# Sheet3.net
KiCad netlist of a schematic drawn in Altium Designer
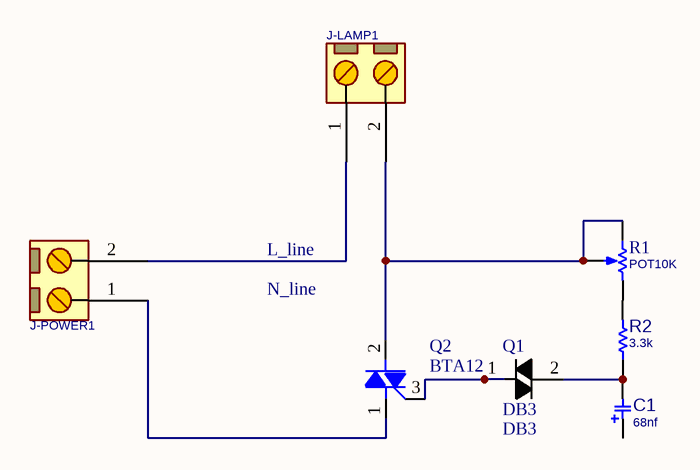
[diagram p0: Sheet3.SchDoc]

(export (version "E")
  (design (tool "Eeschema 10.0.6"))
  (components
    (comp (ref "C1")
      (value "68nf")
      (footprint "C_FLM_7X5H11")
      (description "CAP, THD, FILM,")
      (fields (field (name "MANF_P#") "MANF_PART#") (field (name "MANF") "MANF"))
      (libsource (lib "passive_thd") (part "CAP_THD_FLM"))
    )
    (comp (ref "J-LAMP1")
      (value "CONN_TB2")
      (footprint "MSTB_2")
      (description "CONN, PHOENIX MSTB, 5-G, 5.08mm pitch")
      (libsource (lib "conn_terminalB") (part "CONN_MSTB_2"))
    )
    (comp (ref "J-POWER1")
      (value "CONN_TB2")
      (footprint "MSTB_2")
      (description "CONN, PHOENIX MSTB, 5-G, 5.08mm pitch")
      (libsource (lib "") (part "CONN_MSTB_2_1"))
    )
    (comp (ref "Q1")
      (value "DB3")
      (footprint "D_AX03_DO35")
      (description "Diac, 32VBO, DO-35")
      (fields (field (name "MANF") "ST") (field (name "ALTIUM_VALUE") "DB3"))
      (libsource (lib "triac_diac") (part "DIAC_DB3_DO35"))
    )
    (comp (ref "Q2")
      (value "BTA12")
      (footprint "TO220_3")
      (description "Triac, 600V, 12A, TO-220")
      (fields (field (name "MANF_P#") "BTA12-600BW, BTA12-600CW, BTA12-600TW") (field (name "MANF") "ST"))
      (libsource (lib "triac_diac") (part "TRIAC_BTA12-600_TO220"))
    )
    (comp (ref "R1")
      (value "POT10K")
      (footprint "VOL_R")
      (description "RESISTOR, THD, Potentiometer Volume")
      (libsource (lib "resistor_pot_trimmer") (part "RES_THD_POT_VOL"))
    )
    (comp (ref "R2")
      (value "3.3k")
      (footprint "R025W_AX04")
      (description "RESISTOR, THD")
      (fields (field (name "MANF_P#") "RK73H1ETTP4701F") (field (name "MANF") "KOA SPEER"))
      (libsource (lib "passive_thd") (part "RES_THD"))
    )
  )
  (nets
    (net (code "1") (name "Net-(J-LAMP1-Pad1)") (class "Default")
      (node (ref "J-LAMP1") (pin "1") (pinfunction "1_1") (pintype "passive"))
      (node (ref "J-POWER1") (pin "2") (pinfunction "2_2") (pintype "passive"))
    )
    (net (code "2") (name "Net-(Q1-A1)") (class "Default")
      (node (ref "Q1") (pin "1") (pinfunction "A1_1") (pintype "passive"))
      (node (ref "Q2") (pin "3") (pinfunction "G_3") (pintype "passive"))
    )
    (net (code "3") (name "Net-(Q1-A2)") (class "Default")
      (node (ref "C1") (pin "2") (pinfunction "2_2") (pintype "passive"))
      (node (ref "Q1") (pin "2") (pinfunction "A2_2") (pintype "passive"))
      (node (ref "R2") (pin "1") (pinfunction "1_1") (pintype "passive"))
    )
    (net (code "4") (name "Net-(Q2-T1)") (class "Default")
      (node (ref "J-POWER1") (pin "1") (pinfunction "1_1") (pintype "passive"))
      (node (ref "Q2") (pin "1") (pinfunction "T1_1") (pintype "passive"))
    )
    (net (code "5") (name "Net-(Q2-T2)") (class "Default")
      (node (ref "J-LAMP1") (pin "2") (pinfunction "2_2") (pintype "passive"))
      (node (ref "Q2") (pin "2") (pinfunction "T2_2") (pintype "passive"))
      (node (ref "R1") (pin "1") (pinfunction "TOP_1") (pintype "passive"))
      (node (ref "R1") (pin "2") (pinfunction "TAP_2") (pintype "passive"))
    )
    (net (code "6") (name "Net-(R1-BOT)") (class "Default")
      (node (ref "R1") (pin "3") (pinfunction "BOT_3") (pintype "passive"))
      (node (ref "R2") (pin "2") (pinfunction "2_2") (pintype "passive"))
    )
    (net (code "7") (name "unconnected-(C1-Pad1)") (class "Default")
      (node (ref "C1") (pin "1") (pinfunction "1_1") (pintype "passive"))
    )
  )
)
